# BOT-CPU.net
KiCad netlist of a schematic drawn in Altium Designer
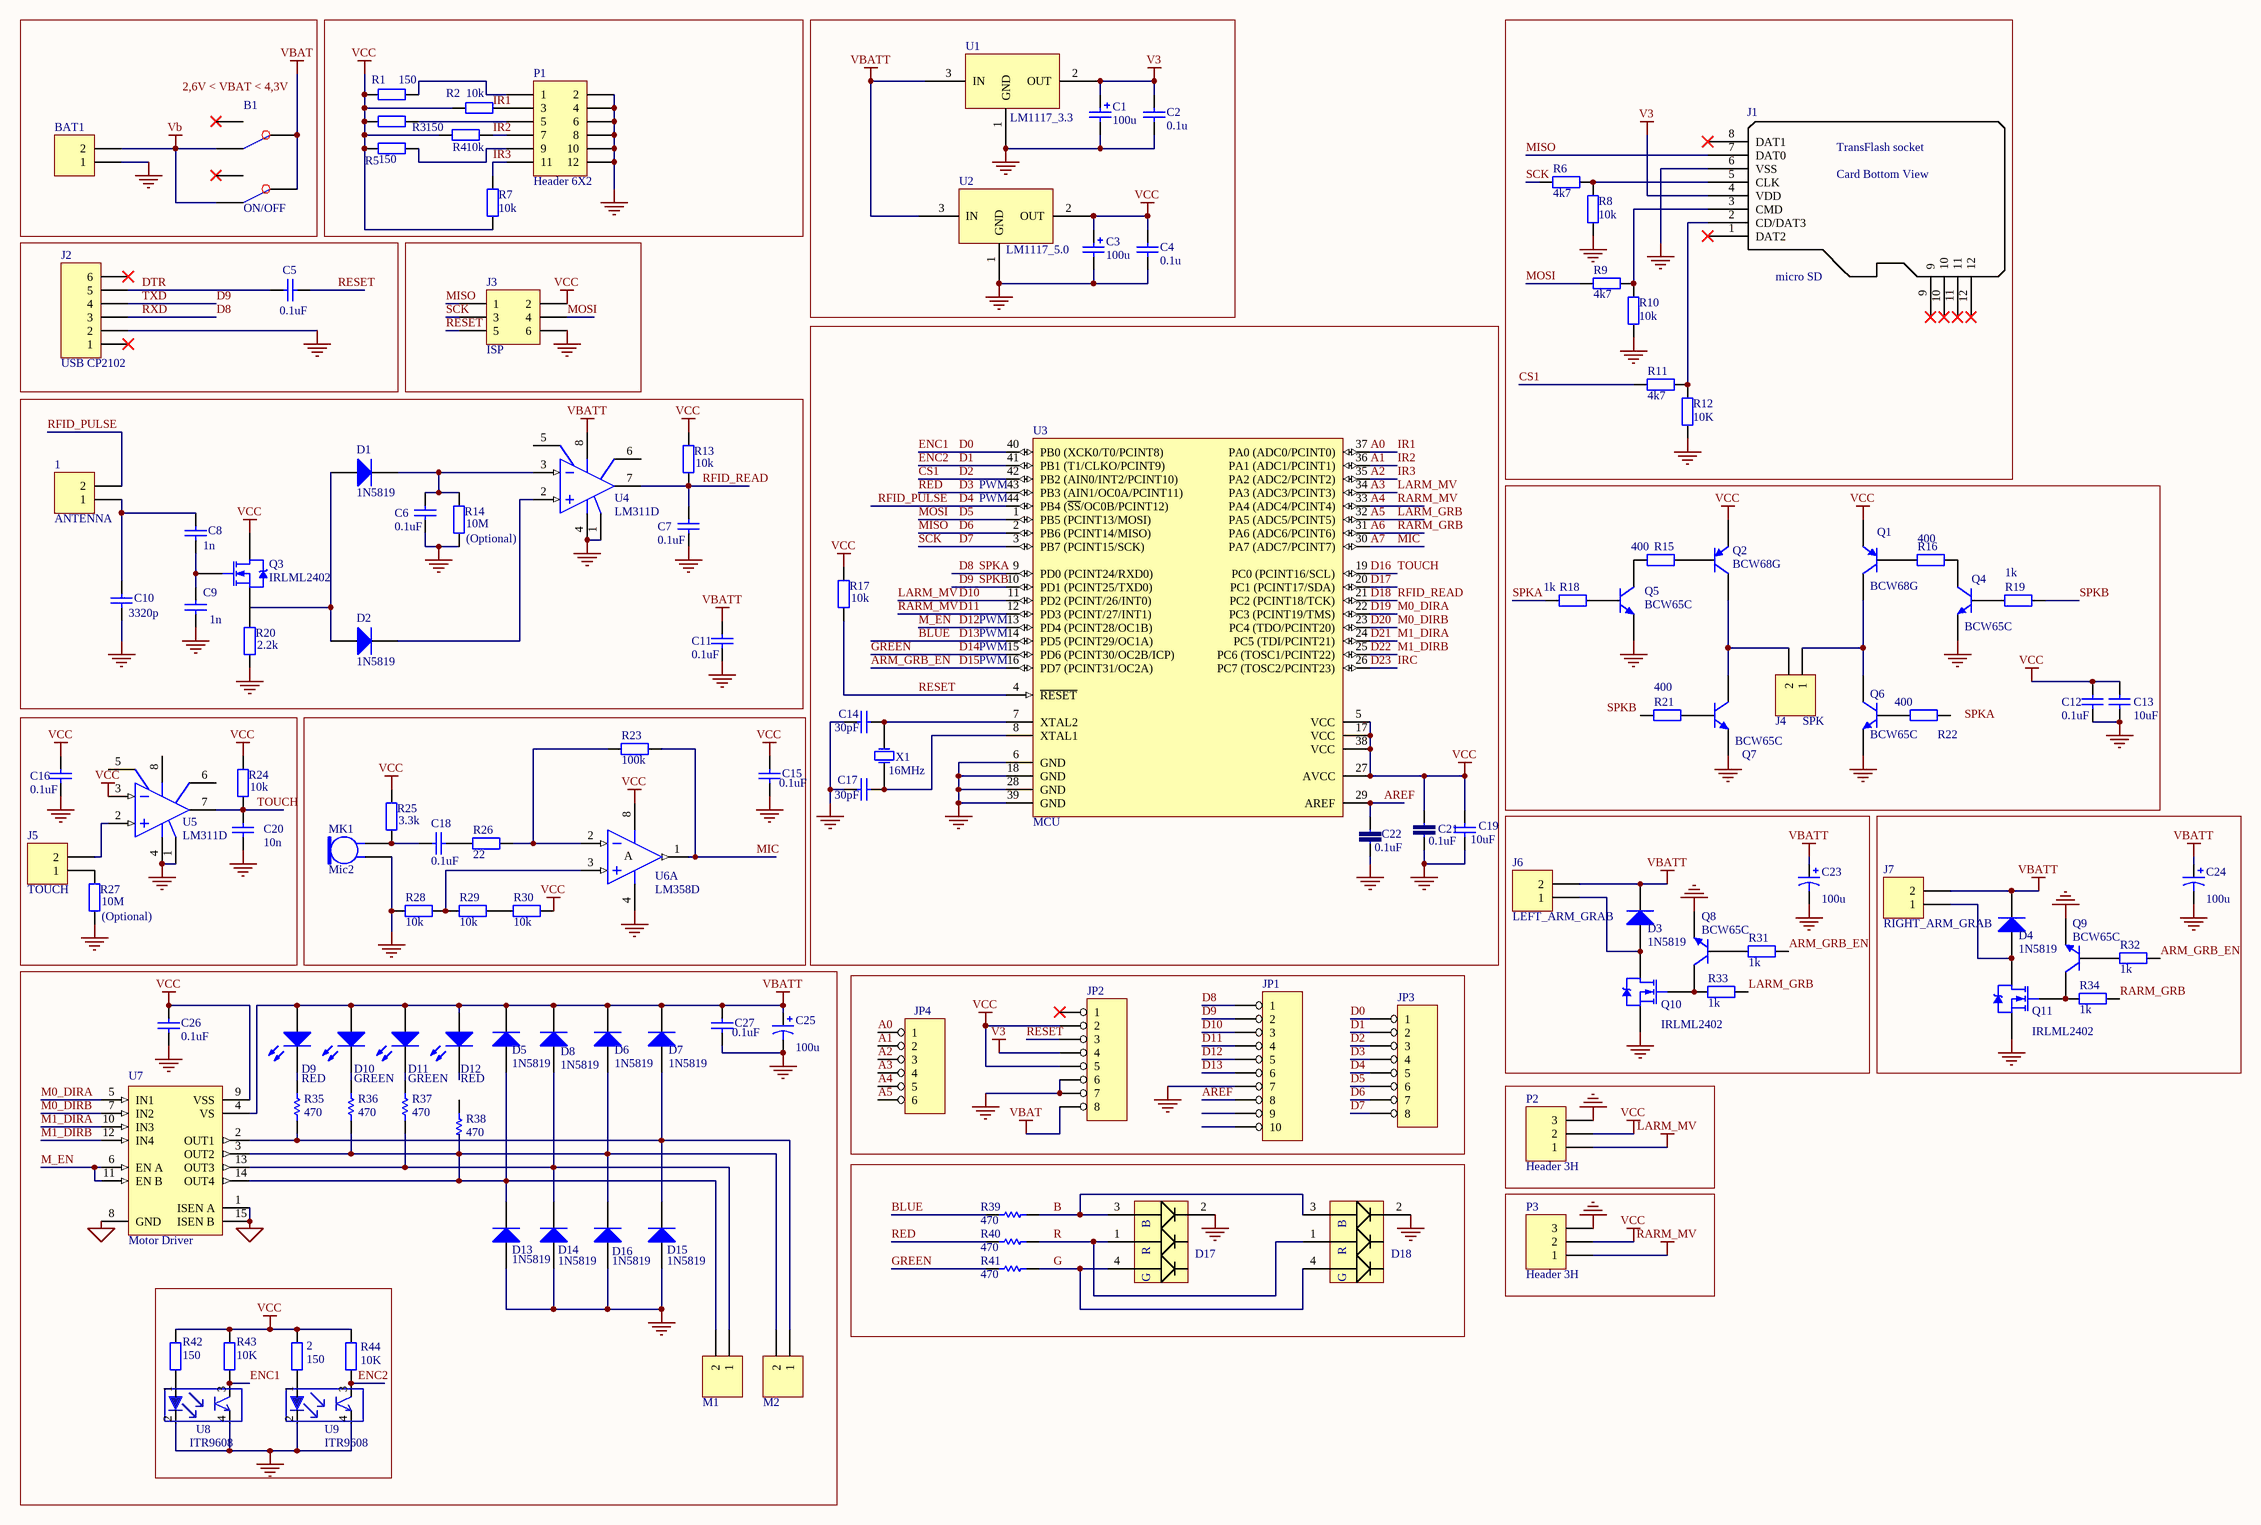
[diagram p0: BOT-CPU.SchDoc]

(export (version "E")
  (design (tool "Eeschema 10.0.6"))
  (components
    (comp (ref "1")
      (value "ANTENNA")
      (footprint "HDR1X2")
      (description "Header, 2-Pin")
      (fields (field (name "PUBLISHER") "Altium Limited"))
      (libsource (lib "*") (part "Header 2"))
    )
    (comp (ref "2")
      (value "150")
      (footprint "0805")
      (description "Resistor")
      (fields (field (name "Comment") "1K") (field (name "PUBLISHER") "Altium Limited"))
      (libsource (lib "") (part "Res2_2"))
    )
    (comp (ref "B1") (value "ON/OFF") (footprint "KGPS22F03") (libsource (lib "*") (part "Component_1")))
    (comp (ref "BAT1")
      (value "Header 2")
      (footprint "CP2D2.54")
      (description "Header, 2-Pin")
      (fields (field (name "PUBLISHER") "Altium Limited"))
      (libsource (lib "*") (part "Header 2"))
    )
    (comp (ref "C1")
      (value "100u")
      (footprint "C(D6.3*7)")
      (description "Polarized Capacitor (Axial)")
      (fields (field (name "ALTIUM_UNNAMED_1") "100u") (field (name "PUBLISHER") "Altium Limited"))
      (libsource (lib "*") (part "Cap Pol2"))
    )
    (comp (ref "C2")
      (value "0.1u")
      (footprint "0805")
      (description "Capacitor")
      (fields (field (name "PUBLISHER") "Altium Limited"))
      (libsource (lib "*") (part "Cap"))
    )
    (comp (ref "C3")
      (value "100u")
      (footprint "C(D6.3*7)")
      (description "Polarized Capacitor (Axial)")
      (fields (field (name "ALTIUM_UNNAMED_1") "100u") (field (name "PUBLISHER") "Altium Limited"))
      (libsource (lib "*") (part "Cap Pol2"))
    )
    (comp (ref "C4")
      (value "0.1u")
      (footprint "0805")
      (description "Capacitor")
      (fields (field (name "PUBLISHER") "Altium Limited"))
      (libsource (lib "*") (part "Cap"))
    )
    (comp (ref "C5")
      (value "0.1uF")
      (footprint "0805")
      (description "Capacitor")
      (fields (field (name "PUBLISHER") "*"))
      (libsource (lib "*") (part "Cap"))
    )
    (comp (ref "C6")
      (value "0.1uF")
      (footprint "0805")
      (description "Capacitor")
      (fields (field (name "PUBLISHER") "Altium Limited"))
      (libsource (lib "*") (part "Cap"))
    )
    (comp (ref "C7")
      (value "0.1uF")
      (footprint "0805")
      (description "Capacitor")
      (fields (field (name "PUBLISHER") "Altium Limited"))
      (libsource (lib "*") (part "Cap"))
    )
    (comp (ref "C8")
      (value "1n")
      (footprint "0805")
      (description "Capacitor")
      (fields (field (name "Comment") "1nF") (field (name "PUBLISHER") "Altium Limited"))
      (libsource (lib "*") (part "Cap"))
    )
    (comp (ref "C9")
      (value "1n")
      (footprint "0805")
      (description "Capacitor")
      (fields (field (name "Comment") "1nF") (field (name "PUBLISHER") "Altium Limited"))
      (libsource (lib "*") (part "Cap"))
    )
    (comp (ref "C10")
      (value "3320p")
      (footprint "0805")
      (description "Capacitor")
      (fields (field (name "Comment") "3320pF") (field (name "PUBLISHER") "Altium Limited"))
      (libsource (lib "*") (part "Cap"))
    )
    (comp (ref "C11")
      (value "0.1uF")
      (footprint "0805")
      (description "Capacitor")
      (fields (field (name "PUBLISHER") "Altium Limited"))
      (libsource (lib "*") (part "Cap"))
    )
    (comp (ref "C12")
      (value "0.1uF")
      (footprint "0805")
      (description "Capacitor")
      (fields (field (name "PUBLISHER") "Altium Limited"))
      (libsource (lib "*") (part "Cap"))
    )
    (comp (ref "C13")
      (value "10uF")
      (footprint "1206")
      (description "Capacitor")
      (fields (field (name "PUBLISHER") "Altium Limited"))
      (libsource (lib "*") (part "Cap"))
    )
    (comp (ref "C14")
      (value "30pF")
      (footprint "0805")
      (description "Capacitor")
      (fields (field (name "PUBLISHER") "Altium Limited"))
      (libsource (lib "*") (part "Cap"))
    )
    (comp (ref "C15")
      (value "0.1uF")
      (footprint "0805")
      (description "Capacitor")
      (fields (field (name "PUBLISHER") "Altium Limited"))
      (libsource (lib "*") (part "Cap"))
    )
    (comp (ref "C16")
      (value "0.1uF")
      (footprint "0805")
      (description "Capacitor")
      (fields (field (name "PUBLISHER") "Altium Limited"))
      (libsource (lib "*") (part "Cap"))
    )
    (comp (ref "C17")
      (value "30pF")
      (footprint "0805")
      (description "Capacitor")
      (fields (field (name "PUBLISHER") "Altium Limited"))
      (libsource (lib "*") (part "Cap"))
    )
    (comp (ref "C18")
      (value "0.1uF")
      (footprint "0805")
      (description "Capacitor")
      (fields (field (name "PUBLISHER") "Altium Limited"))
      (libsource (lib "") (part "Cap_1"))
    )
    (comp (ref "C19")
      (value "10uF")
      (footprint "1206")
      (description "Capacitor")
      (fields (field (name "PUBLISHER") "Altium Limited"))
      (libsource (lib "*") (part "Cap"))
    )
    (comp (ref "C20")
      (value "10n")
      (footprint "0805")
      (description "Capacitor")
      (fields (field (name "Comment") "0.1uF") (field (name "PUBLISHER") "Altium Limited"))
      (libsource (lib "*") (part "Cap"))
    )
    (comp (ref "C21") (value "0.1uF") (footprint "0805") (libsource (lib "*") (part "CAP0402")))
    (comp (ref "C22") (value "0.1uF") (footprint "0805") (libsource (lib "") (part "CAP0402_1")))
    (comp (ref "C23")
      (value "100u")
      (footprint "C(D6.3*7)")
      (description "Polarized Capacitor (Radial)")
      (fields (field (name "Comment") "220u") (field (name "PUBLISHER") "Altium Limited"))
      (libsource (lib "*") (part "Cap Pol1"))
    )
    (comp (ref "C24")
      (value "100u")
      (footprint "C(D6.3*7)")
      (description "Polarized Capacitor (Radial)")
      (fields (field (name "Comment") "220u") (field (name "PUBLISHER") "Altium Limited"))
      (libsource (lib "*") (part "Cap Pol1"))
    )
    (comp (ref "C25")
      (value "100u")
      (footprint "C(D6.3*7)")
      (description "Polarized Capacitor (Radial)")
      (fields (field (name "Comment") "220u") (field (name "PUBLISHER") "Altium Limited"))
      (libsource (lib "*") (part "Cap Pol1"))
    )
    (comp (ref "C26")
      (value "0.1uF")
      (footprint "0805")
      (description "Capacitor")
      (fields (field (name "PUBLISHER") "Altium Limited"))
      (libsource (lib "*") (part "Cap"))
    )
    (comp (ref "C27")
      (value "0.1uF")
      (footprint "0805")
      (description "Capacitor")
      (fields (field (name "PUBLISHER") "Altium Limited"))
      (libsource (lib "*") (part "Cap"))
    )
    (comp (ref "D1")
      (value "1N5819")
      (footprint "4007-smt")
      (description "Default Diode")
      (fields (field (name "PUBLISHER") "Altium Limited"))
      (libsource (lib "*") (part "Diode"))
    )
    (comp (ref "D2")
      (value "1N5819")
      (footprint "4007-smt")
      (description "Default Diode")
      (fields (field (name "PUBLISHER") "Altium Limited"))
      (libsource (lib "*") (part "Diode"))
    )
    (comp (ref "D3")
      (value "1N5819")
      (footprint "4007-smt")
      (description "Default Diode")
      (fields (field (name "PUBLISHER") "Altium Limited"))
      (libsource (lib "*") (part "Diode"))
    )
    (comp (ref "D4")
      (value "1N5819")
      (footprint "4007-smt")
      (description "Default Diode")
      (fields (field (name "PUBLISHER") "Altium Limited"))
      (libsource (lib "*") (part "Diode"))
    )
    (comp (ref "D5")
      (value "1N5819")
      (footprint "4007-smt")
      (description "Default Diode")
      (fields (field (name "PUBLISHER") "Altium Limited"))
      (libsource (lib "*") (part "Diode"))
    )
    (comp (ref "D6")
      (value "1N5819")
      (footprint "4007-smt")
      (description "Default Diode")
      (fields (field (name "PUBLISHER") "Altium Limited"))
      (libsource (lib "*") (part "Diode"))
    )
    (comp (ref "D7")
      (value "1N5819")
      (footprint "4007-smt")
      (description "Default Diode")
      (fields (field (name "PUBLISHER") "Altium Limited"))
      (libsource (lib "*") (part "Diode"))
    )
    (comp (ref "D8")
      (value "1N5819")
      (footprint "4007-smt")
      (description "Default Diode")
      (fields (field (name "PUBLISHER") "*"))
      (libsource (lib "*") (part "Diode"))
    )
    (comp (ref "D9")
      (value "RED")
      (footprint "LED-SMT")
      (description "Typical INFRARED GaAs LED")
      (fields (field (name "PUBLISHER") "Altium Limited"))
      (libsource (lib "*") (part "LED0"))
    )
    (comp (ref "D10")
      (value "GREEN")
      (footprint "LED-SMT")
      (description "Typical INFRARED GaAs LED")
      (fields (field (name "PUBLISHER") "Altium Limited"))
      (libsource (lib "*") (part "LED0"))
    )
    (comp (ref "D11")
      (value "GREEN")
      (footprint "LED-SMT")
      (description "Typical INFRARED GaAs LED")
      (fields (field (name "PUBLISHER") "Altium Limited"))
      (libsource (lib "*") (part "LED0"))
    )
    (comp (ref "D12")
      (value "RED")
      (footprint "LED-SMT")
      (description "Typical INFRARED GaAs LED")
      (fields (field (name "PUBLISHER") "Altium Limited"))
      (libsource (lib "*") (part "LED0"))
    )
    (comp (ref "D13")
      (value "1N5819")
      (footprint "4007-smt")
      (description "Default Diode")
      (fields (field (name "PUBLISHER") "Altium Limited"))
      (libsource (lib "*") (part "Diode"))
    )
    (comp (ref "D14")
      (value "1N5819")
      (footprint "4007-smt")
      (description "Default Diode")
      (fields (field (name "PUBLISHER") "Altium Limited"))
      (libsource (lib "*") (part "Diode"))
    )
    (comp (ref "D15")
      (value "1N5819")
      (footprint "4007-smt")
      (description "Default Diode")
      (fields (field (name "PUBLISHER") "Altium Limited"))
      (libsource (lib "*") (part "Diode"))
    )
    (comp (ref "D16")
      (value "1N5819")
      (footprint "4007-smt")
      (description "Default Diode")
      (fields (field (name "PUBLISHER") "Altium Limited"))
      (libsource (lib "*") (part "Diode"))
    )
    (comp (ref "D17") (value "RGB 5mm") (footprint "LED_RGB") (libsource (lib "*") (part "RGB PTH")))
    (comp (ref "D18") (value "RGB 5mm") (footprint "LED_RGB") (libsource (lib "*") (part "RGB PTH")))
    (comp (ref "J1")
      (value "micro SD")
      (footprint "MICRO_SD")
      (description "Transflash Socket")
      (libsource (lib "*") (part "JJ TRANSFLASH"))
    )
    (comp (ref "J2")
      (value "USB CP2102")
      (footprint "SIP6")
      (description "Header, 6-Pin")
      (fields (field (name "PUBLISHER") "Altium Limited"))
      (libsource (lib "*") (part "Header 6"))
    )
    (comp (ref "J3")
      (value "ISP")
      (footprint "con-6")
      (description "Header, 3-Pin, Dual row")
      (fields (field (name "PUBLISHER") "Altium Limited"))
      (libsource (lib "*") (part "Header 3X2"))
    )
    (comp (ref "J4")
      (value "SPK")
      (footprint "sip2")
      (description "Header, 2-Pin")
      (fields (field (name "PUBLISHER") "Altium Limited"))
      (libsource (lib "") (part "Header 2_1"))
    )
    (comp (ref "J5")
      (value "TOUCH")
      (footprint "HDR1X2")
      (description "Header, 2-Pin")
      (fields (field (name "PUBLISHER") "Altium Limited"))
      (libsource (lib "*") (part "Header 2"))
    )
    (comp (ref "J6")
      (value "LEFT_ARM_GRAB")
      (footprint "HDR1X2")
      (description "Header, 2-Pin")
      (fields (field (name "PUBLISHER") "Altium Limited"))
      (libsource (lib "*") (part "Header 2"))
    )
    (comp (ref "J7")
      (value "RIGHT_ARM_GRAB")
      (footprint "HDR1X2")
      (description "Header, 2-Pin")
      (fields (field (name "PUBLISHER") "Altium Limited"))
      (libsource (lib "*") (part "Header 2"))
    )
    (comp (ref "JP1") (value "PADS") (footprint "ARDUINO_10*1") (libsource (lib "*") (part "HEADER 10")))
    (comp (ref "JP2")
      (value "PADS")
      (footprint "ARDUINO_8*1")
      (description "8 Pin Header")
      (libsource (lib "*") (part "8 HEADER"))
    )
    (comp (ref "JP3")
      (value "PADS")
      (footprint "ARDUINO_8*1")
      (description "8 Pin Header")
      (libsource (lib "*") (part "8 HEADER"))
    )
    (comp (ref "JP4") (value "PADS") (footprint "ARDUINO_6*1") (libsource (lib "*") (part "HEADER 6")))
    (comp (ref "M1")
      (value "MOLEX")
      (footprint "CP2D2.54")
      (description "Header, 2-Pin")
      (fields (field (name "PUBLISHER") "Altium Limited"))
      (libsource (lib "") (part "Header 2_1"))
    )
    (comp (ref "M2")
      (value "MOLEX")
      (footprint "CP2D2.54")
      (description "Header, 2-Pin")
      (fields (field (name "PUBLISHER") "Altium Limited"))
      (libsource (lib "") (part "Header 2_1"))
    )
    (comp (ref "MK1")
      (value "Mic2")
      (footprint "MIC")
      (description "Microphone")
      (fields (field (name "PUBLISHER") "*"))
      (libsource (lib "*") (part "Mic2"))
    )
    (comp (ref "P1")
      (value "Header 6X2")
      (footprint "HDR2X6")
      (description "Header, 6-Pin, Dual row")
      (fields (field (name "PUBLISHER") "Altium Limited"))
      (libsource (lib "Miscellaneous Connectors") (part "Header 6X2"))
    )
    (comp (ref "P2")
      (value "Header 3H")
      (footprint "HDR1X3H")
      (description "Header, 3-Pin, Right Angle")
      (fields (field (name "PUBLISHER") "Altium Limited"))
      (libsource (lib "Miscellaneous Connectors") (part "Header 3H"))
    )
    (comp (ref "P3")
      (value "Header 3H")
      (footprint "HDR1X3H")
      (description "Header, 3-Pin, Right Angle")
      (fields (field (name "PUBLISHER") "Altium Limited"))
      (libsource (lib "Miscellaneous Connectors") (part "Header 3H"))
    )
    (comp (ref "Q1")
      (value "BCW68G")
      (footprint "SOT-23A_N")
      (description "PNP General Purpose Amplifier")
      (fields (field (name "PUBLISHER") "Altium Limited"))
      (libsource (lib "FSC Discrete BJT") (part "BCW68G"))
    )
    (comp (ref "Q2")
      (value "BCW68G")
      (footprint "SOT-23A_N")
      (description "PNP General Purpose Amplifier")
      (fields (field (name "PUBLISHER") "Altium Limited"))
      (libsource (lib "FSC Discrete BJT") (part "BCW68G"))
    )
    (comp (ref "Q3")
      (value "IRLML2402")
      (footprint "SOT-23_N")
      (description "HEXFET Power MOSFET")
      (fields (field (name "PUBLISHER") "Altium Limited"))
      (libsource (lib "IR Discrete MOSFET - Power") (part "IRLML2402"))
    )
    (comp (ref "Q4")
      (value "BCW65C")
      (footprint "SOT-23A_N")
      (description "NPN General Purpose Amplifier")
      (fields (field (name "PUBLISHER") "Altium Limited"))
      (libsource (lib "FSC Discrete BJT") (part "BCW65C"))
    )
    (comp (ref "Q5")
      (value "BCW65C")
      (footprint "SOT-23A_N")
      (description "NPN General Purpose Amplifier")
      (fields (field (name "PUBLISHER") "Altium Limited"))
      (libsource (lib "FSC Discrete BJT") (part "BCW65C"))
    )
    (comp (ref "Q6")
      (value "BCW65C")
      (footprint "SOT-23A_N")
      (description "NPN General Purpose Amplifier")
      (fields (field (name "PUBLISHER") "Altium Limited"))
      (libsource (lib "FSC Discrete BJT") (part "BCW65C"))
    )
    (comp (ref "Q7")
      (value "BCW65C")
      (footprint "SOT-23A_N")
      (description "NPN General Purpose Amplifier")
      (fields (field (name "PUBLISHER") "Altium Limited"))
      (libsource (lib "FSC Discrete BJT") (part "BCW65C"))
    )
    (comp (ref "Q8")
      (value "BCW65C")
      (footprint "SOT-23A_N")
      (description "NPN General Purpose Amplifier")
      (fields (field (name "PUBLISHER") "Altium Limited"))
      (libsource (lib "FSC Discrete BJT") (part "BCW65C"))
    )
    (comp (ref "Q9")
      (value "BCW65C")
      (footprint "SOT-23A_N")
      (description "NPN General Purpose Amplifier")
      (fields (field (name "PUBLISHER") "Altium Limited"))
      (libsource (lib "FSC Discrete BJT") (part "BCW65C"))
    )
    (comp (ref "Q10")
      (value "IRLML2402")
      (footprint "SOT-23_N")
      (description "HEXFET Power MOSFET")
      (fields (field (name "PUBLISHER") "Altium Limited"))
      (libsource (lib "IR Discrete MOSFET - Power") (part "IRLML2402"))
    )
    (comp (ref "Q11")
      (value "IRLML2402")
      (footprint "SOT-23_N")
      (description "HEXFET Power MOSFET")
      (fields (field (name "PUBLISHER") "Altium Limited"))
      (libsource (lib "IR Discrete MOSFET - Power") (part "IRLML2402"))
    )
    (comp (ref "R1")
      (value "150")
      (footprint "0805")
      (description "Resistor")
      (fields (field (name "PUBLISHER") "Altium Limited"))
      (libsource (lib "") (part "Res2_3"))
    )
    (comp (ref "R2")
      (value "10k")
      (footprint "0805")
      (description "Resistor")
      (fields (field (name "PUBLISHER") "Altium Limited"))
      (libsource (lib "") (part "Res2_3"))
    )
    (comp (ref "R3")
      (value "150")
      (footprint "0805")
      (description "Resistor")
      (fields (field (name "PUBLISHER") "Altium Limited"))
      (libsource (lib "") (part "Res2_3"))
    )
    (comp (ref "R4")
      (value "10k")
      (footprint "0805")
      (description "Resistor")
      (fields (field (name "PUBLISHER") "Altium Limited"))
      (libsource (lib "") (part "Res2_3"))
    )
    (comp (ref "R5")
      (value "150")
      (footprint "0805")
      (description "Resistor")
      (fields (field (name "PUBLISHER") "Altium Limited"))
      (libsource (lib "") (part "Res2_3"))
    )
    (comp (ref "R6")
      (value "4k7")
      (footprint "0805")
      (description "Resistor")
      (fields (field (name "PUBLISHER") "Altium Limited"))
      (libsource (lib "*") (part "Res2"))
    )
    (comp (ref "R7")
      (value "10k")
      (footprint "0805")
      (description "Resistor")
      (fields (field (name "PUBLISHER") "Altium Limited"))
      (libsource (lib "") (part "Res2_2"))
    )
    (comp (ref "R8")
      (value "10k")
      (footprint "0805")
      (description "Resistor")
      (fields (field (name "PUBLISHER") "Altium Limited"))
      (libsource (lib "") (part "Res2_1"))
    )
    (comp (ref "R9")
      (value "4k7")
      (footprint "0805")
      (description "Resistor")
      (fields (field (name "Comment") "10k") (field (name "PUBLISHER") "Altium Limited"))
      (libsource (lib "*") (part "Res2"))
    )
    (comp (ref "R10")
      (value "10k")
      (footprint "0805")
      (description "Resistor")
      (fields (field (name "Comment") "20K") (field (name "PUBLISHER") "Altium Limited"))
      (libsource (lib "") (part "Res2_1"))
    )
    (comp (ref "R11")
      (value "4k7")
      (footprint "0805")
      (description "Resistor")
      (fields (field (name "Comment") "10k") (field (name "PUBLISHER") "Altium Limited"))
      (libsource (lib "") (part "Res2_1"))
    )
    (comp (ref "R12")
      (value "10K")
      (footprint "0805")
      (description "Resistor")
      (fields (field (name "PUBLISHER") "Altium Limited"))
      (libsource (lib "*") (part "Res2"))
    )
    (comp (ref "R13")
      (value "10k")
      (footprint "0805")
      (description "Resistor")
      (fields (field (name "PUBLISHER") "Altium Limited"))
      (libsource (lib "*") (part "Res2"))
    )
    (comp (ref "R14")
      (value "(Optional)")
      (footprint "0805")
      (description "Resistor")
      (fields (field (name "ALTIUM_VALUE") "10M") (field (name "PUBLISHER") "Altium Limited"))
      (libsource (lib "*") (part "Res2"))
    )
    (comp (ref "R15")
      (value "400")
      (footprint "0805")
      (description "Resistor")
      (fields (field (name "PUBLISHER") "Altium Limited"))
      (libsource (lib "") (part "Res2_3"))
    )
    (comp (ref "R16")
      (value "400")
      (footprint "0805")
      (description "Resistor")
      (fields (field (name "PUBLISHER") "Altium Limited"))
      (libsource (lib "*") (part "Res2"))
    )
    (comp (ref "R17")
      (value "10k")
      (footprint "0805")
      (description "Resistor")
      (fields (field (name "Comment") "2.2k") (field (name "PUBLISHER") "Altium Limited"))
      (libsource (lib "*") (part "Res2"))
    )
    (comp (ref "R18")
      (value "1k")
      (footprint "0805")
      (description "Resistor")
      (fields (field (name "Comment") "1K") (field (name "PUBLISHER") "Altium Limited"))
      (libsource (lib "") (part "Res2_3"))
    )
    (comp (ref "R19")
      (value "1k")
      (footprint "0805")
      (description "Resistor")
      (fields (field (name "Comment") "1K") (field (name "PUBLISHER") "Altium Limited"))
      (libsource (lib "*") (part "Res2"))
    )
    (comp (ref "R20")
      (value "2.2k")
      (footprint "0805")
      (description "Resistor")
      (fields (field (name "PUBLISHER") "Altium Limited"))
      (libsource (lib "*") (part "Res2"))
    )
    (comp (ref "R21")
      (value "400")
      (footprint "0805")
      (description "Resistor")
      (fields (field (name "PUBLISHER") "Altium Limited"))
      (libsource (lib "") (part "Res2_3"))
    )
    (comp (ref "R22")
      (value "400")
      (footprint "0805")
      (description "Resistor")
      (fields (field (name "PUBLISHER") "Altium Limited"))
      (libsource (lib "*") (part "Res2"))
    )
    (comp (ref "R23")
      (value "100k")
      (footprint "0805")
      (description "Resistor")
      (fields (field (name "Comment") "1M") (field (name "PUBLISHER") "Altium Limited"))
      (libsource (lib "") (part "Res2_3"))
    )
    (comp (ref "R24")
      (value "10k")
      (footprint "0805")
      (description "Resistor")
      (fields (field (name "PUBLISHER") "Altium Limited"))
      (libsource (lib "*") (part "Res2"))
    )
    (comp (ref "R25")
      (value "3.3k")
      (footprint "0805")
      (description "Resistor")
      (fields (field (name "PUBLISHER") "Altium Limited"))
      (libsource (lib "*") (part "Res2"))
    )
    (comp (ref "R26")
      (value "22")
      (footprint "0805")
      (description "Resistor")
      (fields (field (name "PUBLISHER") "Altium Limited"))
      (libsource (lib "") (part "Res2_3"))
    )
    (comp (ref "R27")
      (value "(Optional)")
      (footprint "0805")
      (description "Resistor")
      (fields (field (name "ALTIUM_VALUE") "10M") (field (name "PUBLISHER") "Altium Limited"))
      (libsource (lib "*") (part "Res2"))
    )
    (comp (ref "R28")
      (value "10k")
      (footprint "0805")
      (description "Resistor")
      (fields (field (name "PUBLISHER") "Altium Limited"))
      (libsource (lib "") (part "Res2_3"))
    )
    (comp (ref "R29")
      (value "10k")
      (footprint "0805")
      (description "Resistor")
      (fields (field (name "PUBLISHER") "Altium Limited"))
      (libsource (lib "") (part "Res2_3"))
    )
    (comp (ref "R30")
      (value "10k")
      (footprint "0805")
      (description "Resistor")
      (fields (field (name "PUBLISHER") "Altium Limited"))
      (libsource (lib "") (part "Res2_3"))
    )
    (comp (ref "R31")
      (value "1k")
      (footprint "0805")
      (description "Resistor")
      (fields (field (name "Comment") "2.2k") (field (name "PUBLISHER") "Altium Limited"))
      (libsource (lib "") (part "Res2_3"))
    )
    (comp (ref "R32")
      (value "1k")
      (footprint "0805")
      (description "Resistor")
      (fields (field (name "Comment") "2.2k") (field (name "PUBLISHER") "Altium Limited"))
      (libsource (lib "") (part "Res2_3"))
    )
    (comp (ref "R33")
      (value "1k")
      (footprint "0805")
      (description "Resistor")
      (fields (field (name "Comment") "2.2k") (field (name "PUBLISHER") "Altium Limited"))
      (libsource (lib "") (part "Res2_3"))
    )
    (comp (ref "R34")
      (value "1k")
      (footprint "0805")
      (description "Resistor")
      (fields (field (name "Comment") "2.2k") (field (name "PUBLISHER") "Altium Limited"))
      (libsource (lib "") (part "Res2_3"))
    )
    (comp (ref "R35")
      (value "470")
      (footprint "0805")
      (description "Resistor")
      (fields (field (name "PUBLISHER") "Altium Limited"))
      (libsource (lib "*") (part "Res1"))
    )
    (comp (ref "R36")
      (value "470")
      (footprint "0805")
      (description "Resistor")
      (fields (field (name "PUBLISHER") "Altium Limited"))
      (libsource (lib "*") (part "Res1"))
    )
    (comp (ref "R37")
      (value "470")
      (footprint "0805")
      (description "Resistor")
      (fields (field (name "PUBLISHER") "Altium Limited"))
      (libsource (lib "*") (part "Res1"))
    )
    (comp (ref "R38")
      (value "470")
      (footprint "0805")
      (description "Resistor")
      (fields (field (name "PUBLISHER") "Altium Limited"))
      (libsource (lib "*") (part "Res1"))
    )
    (comp (ref "R39")
      (value "470")
      (footprint "0805")
      (description "Resistor")
      (fields (field (name "Comment") "560") (field (name "PUBLISHER") "Altium Limited"))
      (libsource (lib "*") (part "Res1"))
    )
    (comp (ref "R40")
      (value "470")
      (footprint "0805")
      (description "Resistor")
      (fields (field (name "PUBLISHER") "Altium Limited"))
      (libsource (lib "*") (part "Res1"))
    )
    (comp (ref "R41")
      (value "470")
      (footprint "0805")
      (description "Resistor")
      (fields (field (name "PUBLISHER") "Altium Limited"))
      (libsource (lib "*") (part "Res1"))
    )
    (comp (ref "R42")
      (value "150")
      (footprint "0805")
      (description "Resistor")
      (fields (field (name "Comment") "1K") (field (name "PUBLISHER") "Altium Limited"))
      (libsource (lib "") (part "Res2_2"))
    )
    (comp (ref "R43")
      (value "10K")
      (footprint "0805")
      (description "Resistor")
      (fields (field (name "Comment") "1K") (field (name "PUBLISHER") "Altium Limited"))
      (libsource (lib "") (part "Res2_2"))
    )
    (comp (ref "R44")
      (value "10K")
      (footprint "0805")
      (description "Resistor")
      (fields (field (name "Comment") "1K") (field (name "PUBLISHER") "Altium Limited"))
      (libsource (lib "") (part "Res2_2"))
    )
    (comp (ref "U1") (value "LM1117_3.3") (footprint "LM1117") (libsource (lib "*") (part "LM1117")))
    (comp (ref "U2") (value "LM1117_5.0") (footprint "LM1117") (libsource (lib "*") (part "LM1117")))
    (comp (ref "U3")
      (value "MCU")
      (footprint "QFP44")
      (description "8-bit AVR Microcontroller, 2.7-5.5V, 20MHz, 64KB Flash, 2KB EEPROM, 4KB SRAM, 44-pin TQFP")
      (libsource (lib "*") (part "ATmega644-20AU"))
    )
    (comp (ref "U4")
      (value "LM311D")
      (footprint "SO8_N")
      (description "Voltage Comparator")
      (fields (field (name "PUBLISHER") "Altium Limited"))
      (libsource (lib "ST Analog Comparator") (part "LM311D"))
    )
    (comp (ref "U5")
      (value "LM311D")
      (footprint "SO8_N")
      (description "Voltage Comparator")
      (fields (field (name "PUBLISHER") "Altium Limited"))
      (libsource (lib "ST Analog Comparator") (part "LM311D"))
    )
    (comp (ref "U6")
      (value "LM358D")
      (footprint "D008_L")
      (description "Dual Operational Amplifier")
      (fields (field (name "PUBLISHER") "Altium Limited"))
      (libsource (lib "TI Operational Amplifier") (part "LM358D"))
    )
    (comp (ref "U7")
      (value "Motor Driver")
      (footprint "L298N")
      (description "Dual Full Bridge Driver")
      (fields (field (name "PUBLISHER") "Altium Limited"))
      (libsource (lib "*") (part "L298N"))
    )
    (comp (ref "U8") (value "ITR9608") (footprint "ITR9608") (libsource (lib "*") (part "ITR9608")))
    (comp (ref "U9") (value "ITR9608") (footprint "ITR9608") (libsource (lib "*") (part "ITR9608")))
    (comp (ref "X1")
      (value "16MHz")
      (footprint "XTAL2")
      (description "Crystal Oscillator")
      (fields (field (name "PUBLISHER") "Altium Limited"))
      (libsource (lib "*") (part "XTAL"))
    )
  )
  (nets
    (net (code "1") (name "/A0") (class "Default")
      (node (ref "JP4") (pin "1") (pinfunction "1_1") (pintype "passive"))
      (node (ref "U3") (pin "37") (pinfunction "PA0_(ADC0/PCINT0)_37") (pintype "bidirectional"))
    )
    (net (code "2") (name "/A1") (class "Default")
      (node (ref "JP4") (pin "2") (pinfunction "2_2") (pintype "passive"))
      (node (ref "P1") (pin "7") (pinfunction "7_7") (pintype "passive"))
      (node (ref "R4") (pin "2") (pinfunction "2_2") (pintype "passive"))
      (node (ref "U3") (pin "36") (pinfunction "PA1_(ADC1/PCINT1)_36") (pintype "bidirectional"))
    )
    (net (code "3") (name "/A2") (class "Default")
      (node (ref "JP4") (pin "3") (pinfunction "3_3") (pintype "passive"))
      (node (ref "P1") (pin "11") (pinfunction "11_11") (pintype "passive"))
      (node (ref "R7") (pin "2") (pinfunction "2_2") (pintype "passive"))
      (node (ref "U3") (pin "35") (pinfunction "PA2_(ADC2/PCINT2)_35") (pintype "bidirectional"))
    )
    (net (code "4") (name "/A5") (class "Default")
      (node (ref "JP4") (pin "6") (pinfunction "6_6") (pintype "passive"))
      (node (ref "R33") (pin "2") (pinfunction "2_2") (pintype "passive"))
      (node (ref "U3") (pin "32") (pinfunction "PA5_(ADC5/PCINT5)_32") (pintype "bidirectional"))
    )
    (net (code "5") (name "/A6") (class "Default")
      (node (ref "R34") (pin "2") (pinfunction "2_2") (pintype "passive"))
      (node (ref "U3") (pin "31") (pinfunction "PA6_(ADC6/PCINT6)_31") (pintype "bidirectional"))
    )
    (net (code "6") (name "/A7") (class "Default")
      (node (ref "R23") (pin "2") (pinfunction "2_2") (pintype "passive"))
      (node (ref "U3") (pin "30") (pinfunction "PA7_(ADC7/PCINT7)_30") (pintype "bidirectional"))
      (node (ref "U6") (pin "1") (pinfunction "OUT_1") (pintype "output"))
    )
    (net (code "7") (name "/AREF") (class "Default")
      (node (ref "C22") (pin "2") (pinfunction "2_2") (pintype "passive"))
      (node (ref "JP1") (pin "8") (pinfunction "8_8") (pintype "passive"))
      (node (ref "U3") (pin "29") (pinfunction "AREF_29") (pintype "passive"))
    )
    (net (code "8") (name "/ARM_GRB_EN") (class "Default")
      (node (ref "R31") (pin "2") (pinfunction "2_2") (pintype "passive"))
      (node (ref "R32") (pin "2") (pinfunction "2_2") (pintype "passive"))
      (node (ref "U3") (pin "16") (pinfunction "PD7_(PCINT31/OC2A)_16") (pintype "bidirectional"))
    )
    (net (code "9") (name "/B") (class "Default")
      (node (ref "D17") (pin "3") (pinfunction "3_3") (pintype "passive"))
      (node (ref "D18") (pin "3") (pinfunction "3_3") (pintype "passive"))
      (node (ref "R39") (pin "2") (pinfunction "2_2") (pintype "passive"))
    )
    (net (code "10") (name "/BLUE") (class "Default")
      (node (ref "JP1") (pin "6") (pinfunction "6_6") (pintype "passive"))
      (node (ref "R39") (pin "1") (pinfunction "1_1") (pintype "passive"))
      (node (ref "U3") (pin "14") (pinfunction "PD5_(PCINT29/OC1A)_14") (pintype "bidirectional"))
    )
    (net (code "11") (name "/CS1") (class "Default")
      (node (ref "JP3") (pin "3") (pinfunction "3_3") (pintype "passive"))
      (node (ref "R11") (pin "2") (pinfunction "2_2") (pintype "passive"))
      (node (ref "U3") (pin "42") (pinfunction "PB2_(AIN0/INT2/PCINT10)_42") (pintype "bidirectional"))
    )
    (net (code "12") (name "/D0") (class "Default")
      (node (ref "JP3") (pin "1") (pinfunction "1_1") (pintype "passive"))
      (node (ref "R43") (pin "1") (pinfunction "1_1") (pintype "passive"))
      (node (ref "U3") (pin "40") (pinfunction "PB0_(XCK0/T0/PCINT8)_40") (pintype "bidirectional"))
      (node (ref "U8") (pin "3") (pinfunction "COLLECTOR_3") (pintype "passive"))
    )
    (net (code "13") (name "/D1") (class "Default")
      (node (ref "JP3") (pin "2") (pinfunction "2_2") (pintype "passive"))
      (node (ref "R44") (pin "1") (pinfunction "1_1") (pintype "passive"))
      (node (ref "U3") (pin "41") (pinfunction "PB1_(T1/CLKO/PCINT9)_41") (pintype "bidirectional"))
      (node (ref "U9") (pin "3") (pinfunction "COLLECTOR_3") (pintype "passive"))
    )
    (net (code "14") (name "/D3") (class "Default")
      (node (ref "JP3") (pin "4") (pinfunction "4_4") (pintype "passive"))
      (node (ref "R40") (pin "1") (pinfunction "1_1") (pintype "passive"))
      (node (ref "U3") (pin "43") (pinfunction "PB3_(AIN1/OC0A/PCINT11)_43") (pintype "bidirectional"))
    )
    (net (code "15") (name "/D4") (class "Default")
      (node (ref "1") (pin "2") (pinfunction "2_2") (pintype "passive"))
      (node (ref "JP3") (pin "5") (pinfunction "5_5") (pintype "passive"))
      (node (ref "U3") (pin "44") (pinfunction "PB4_(~{SS}/OC0B/PCINT12)_44") (pintype "bidirectional"))
    )
    (net (code "16") (name "/D5") (class "Default")
      (node (ref "J3") (pin "4") (pinfunction "4_4") (pintype "passive"))
      (node (ref "JP3") (pin "6") (pinfunction "6_6") (pintype "passive"))
      (node (ref "R9") (pin "2") (pinfunction "2_2") (pintype "passive"))
      (node (ref "U3") (pin "1") (pinfunction "PB5_(PCINT13/MOSI)_1") (pintype "bidirectional"))
    )
    (net (code "17") (name "/D6") (class "Default")
      (node (ref "J1") (pin "7") (pinfunction "DAT0_7") (pintype "passive"))
      (node (ref "J3") (pin "1") (pinfunction "1_1") (pintype "passive"))
      (node (ref "JP3") (pin "7") (pinfunction "7_7") (pintype "passive"))
      (node (ref "U3") (pin "2") (pinfunction "PB6_(PCINT14/MISO)_2") (pintype "bidirectional"))
    )
    (net (code "18") (name "/D7") (class "Default")
      (node (ref "J3") (pin "3") (pinfunction "3_3") (pintype "passive"))
      (node (ref "JP3") (pin "8") (pinfunction "8_8") (pintype "passive"))
      (node (ref "R6") (pin "2") (pinfunction "2_2") (pintype "passive"))
      (node (ref "U3") (pin "3") (pinfunction "PB7_(PCINT15/SCK)_3") (pintype "bidirectional"))
    )
    (net (code "19") (name "/D8") (class "Default")
      (node (ref "J2") (pin "3") (pinfunction "3_3") (pintype "passive"))
      (node (ref "JP1") (pin "1") (pinfunction "1_1") (pintype "passive"))
      (node (ref "R18") (pin "1") (pinfunction "1_1") (pintype "passive"))
      (node (ref "U3") (pin "9") (pinfunction "PD0_(PCINT24/RXD0)_9") (pintype "bidirectional"))
    )
    (net (code "20") (name "/D9") (class "Default")
      (node (ref "J2") (pin "4") (pinfunction "4_4") (pintype "passive"))
      (node (ref "JP1") (pin "2") (pinfunction "2_2") (pintype "passive"))
      (node (ref "R19") (pin "1") (pinfunction "1_1") (pintype "passive"))
      (node (ref "U3") (pin "10") (pinfunction "PD1_(PCINT25/TXD0)_10") (pintype "bidirectional"))
    )
    (net (code "21") (name "/D12") (class "Default")
      (node (ref "JP1") (pin "5") (pinfunction "5_5") (pintype "passive"))
      (node (ref "U3") (pin "13") (pinfunction "PD4_(PCINT28/OC1B)_13") (pintype "bidirectional"))
      (node (ref "U7") (pin "11") (pinfunction "EN_B_11") (pintype "input"))
      (node (ref "U7") (pin "6") (pinfunction "EN_A_6") (pintype "input"))
    )
    (net (code "22") (name "/D14") (class "Default")
      (node (ref "R41") (pin "1") (pinfunction "1_1") (pintype "passive"))
      (node (ref "U3") (pin "15") (pinfunction "PD6_(PCINT30/OC2B/ICP)_15") (pintype "bidirectional"))
    )
    (net (code "23") (name "/D16") (class "Default")
      (node (ref "C20") (pin "2") (pinfunction "2_2") (pintype "passive"))
      (node (ref "R24") (pin "2") (pinfunction "2_2") (pintype "passive"))
      (node (ref "U3") (pin "19") (pinfunction "PC0_(PCINT16/SCL)_19") (pintype "bidirectional"))
      (node (ref "U5") (pin "7") (pinfunction "OUT_7") (pintype "open_collector"))
    )
    (net (code "24") (name "/D17") (class "Default")
      (node (ref "U3") (pin "20") (pinfunction "PC1_(PCINT17/SDA)_20") (pintype "bidirectional"))
    )
    (net (code "25") (name "/D18") (class "Default")
      (node (ref "C7") (pin "2") (pinfunction "2_2") (pintype "passive"))
      (node (ref "R13") (pin "2") (pinfunction "2_2") (pintype "passive"))
      (node (ref "U3") (pin "21") (pinfunction "PC2_(PCINT18/TCK)_21") (pintype "bidirectional"))
      (node (ref "U4") (pin "7") (pinfunction "OUT_7") (pintype "open_collector"))
    )
    (net (code "26") (name "/D19") (class "Default")
      (node (ref "U3") (pin "22") (pinfunction "PC3_(PCINT19/TMS)_22") (pintype "bidirectional"))
      (node (ref "U7") (pin "5") (pinfunction "IN1_5") (pintype "input"))
    )
    (net (code "27") (name "/D20") (class "Default")
      (node (ref "U3") (pin "23") (pinfunction "PC4_(TDO/PCINT20)_23") (pintype "bidirectional"))
      (node (ref "U7") (pin "7") (pinfunction "IN2_7") (pintype "input"))
    )
    (net (code "28") (name "/D21") (class "Default")
      (node (ref "U3") (pin "24") (pinfunction "PC5_(TDI/PCINT21)_24") (pintype "bidirectional"))
      (node (ref "U7") (pin "10") (pinfunction "IN3_10") (pintype "input"))
    )
    (net (code "29") (name "/D22") (class "Default")
      (node (ref "U3") (pin "25") (pinfunction "PC6_(TOSC1/PCINT22)_25") (pintype "bidirectional"))
      (node (ref "U7") (pin "12") (pinfunction "IN4_12") (pintype "input"))
    )
    (net (code "30") (name "/D23") (class "Default")
      (node (ref "U3") (pin "26") (pinfunction "PC7_(TOSC2/PCINT23)_26") (pintype "bidirectional"))
    )
    (net (code "31") (name "/DTR") (class "Default")
      (node (ref "C5") (pin "1") (pinfunction "1_1") (pintype "passive"))
      (node (ref "J2") (pin "5") (pinfunction "5_5") (pintype "passive"))
    )
    (net (code "32") (name "/G") (class "Default")
      (node (ref "D17") (pin "4") (pinfunction "4_4") (pintype "passive"))
      (node (ref "D18") (pin "4") (pinfunction "4_4") (pintype "passive"))
      (node (ref "R41") (pin "2") (pinfunction "2_2") (pintype "passive"))
    )
    (net (code "33") (name "/R") (class "Default")
      (node (ref "D17") (pin "1") (pinfunction "1_1") (pintype "passive"))
      (node (ref "D18") (pin "1") (pinfunction "1_1") (pintype "passive"))
      (node (ref "R40") (pin "2") (pinfunction "2_2") (pintype "passive"))
    )
    (net (code "34") (name "/RESET") (class "Default")
      (node (ref "C5") (pin "2") (pinfunction "2_2") (pintype "passive"))
      (node (ref "J3") (pin "5") (pinfunction "5_5") (pintype "passive"))
      (node (ref "JP2") (pin "3") (pinfunction "3_3") (pintype "passive"))
      (node (ref "R17") (pin "2") (pinfunction "2_2") (pintype "passive"))
      (node (ref "U3") (pin "4") (pinfunction "~{RESET}_4") (pintype "input"))
    )
    (net (code "35") (name "GND") (class "Default")
      (node (ref "BAT1") (pin "1") (pinfunction "1_1") (pintype "passive"))
      (node (ref "C1") (pin "2") (pinfunction "2_2") (pintype "passive"))
      (node (ref "C10") (pin "1") (pinfunction "1_1") (pintype "passive"))
      (node (ref "C11") (pin "1") (pinfunction "1_1") (pintype "passive"))
      (node (ref "C12") (pin "1") (pinfunction "1_1") (pintype "passive"))
      (node (ref "C13") (pin "1") (pinfunction "1_1") (pintype "passive"))
      (node (ref "C14") (pin "1") (pinfunction "1_1") (pintype "passive"))
      (node (ref "C15") (pin "2") (pinfunction "2_2") (pintype "passive"))
      (node (ref "C16") (pin "1") (pinfunction "1_1") (pintype "passive"))
      (node (ref "C17") (pin "1") (pinfunction "1_1") (pintype "passive"))
      (node (ref "C19") (pin "1") (pinfunction "1_1") (pintype "passive"))
      (node (ref "C2") (pin "1") (pinfunction "1_1") (pintype "passive"))
      (node (ref "C20") (pin "1") (pinfunction "1_1") (pintype "passive"))
      (node (ref "C21") (pin "1") (pinfunction "1_1") (pintype "passive"))
      (node (ref "C22") (pin "1") (pinfunction "1_1") (pintype "passive"))
      (node (ref "C23") (pin "2") (pinfunction "2_2") (pintype "passive"))
      (node (ref "C24") (pin "2") (pinfunction "2_2") (pintype "passive"))
      (node (ref "C25") (pin "2") (pinfunction "2_2") (pintype "passive"))
      (node (ref "C26") (pin "2") (pinfunction "2_2") (pintype "passive"))
      (node (ref "C27") (pin "2") (pinfunction "2_2") (pintype "passive"))
      (node (ref "C3") (pin "2") (pinfunction "2_2") (pintype "passive"))
      (node (ref "C4") (pin "1") (pinfunction "1_1") (pintype "passive"))
      (node (ref "C6") (pin "1") (pinfunction "1_1") (pintype "passive"))
      (node (ref "C7") (pin "1") (pinfunction "1_1") (pintype "passive"))
      (node (ref "C9") (pin "1") (pinfunction "1_1") (pintype "passive"))
      (node (ref "D13") (pin "1") (pinfunction "A_1") (pintype "passive"))
      (node (ref "D14") (pin "1") (pinfunction "A_1") (pintype "passive"))
      (node (ref "D15") (pin "1") (pinfunction "A_1") (pintype "passive"))
      (node (ref "D16") (pin "1") (pinfunction "A_1") (pintype "passive"))
      (node (ref "D17") (pin "2") (pinfunction "2_2") (pintype "passive"))
      (node (ref "D18") (pin "2") (pinfunction "2_2") (pintype "passive"))
      (node (ref "J1") (pin "6") (pinfunction "VSS_6") (pintype "passive"))
      (node (ref "J2") (pin "2") (pinfunction "2_2") (pintype "passive"))
      (node (ref "J3") (pin "6") (pinfunction "6_6") (pintype "passive"))
      (node (ref "JP1") (pin "7") (pinfunction "7_7") (pintype "passive"))
      (node (ref "JP2") (pin "6") (pinfunction "6_6") (pintype "passive"))
      (node (ref "JP2") (pin "7") (pinfunction "7_7") (pintype "passive"))
      (node (ref "MK1") (pin "2") (pinfunction "2_2") (pintype "passive"))
      (node (ref "P1") (pin "10") (pinfunction "10_10") (pintype "passive"))
      (node (ref "P1") (pin "12") (pinfunction "12_12") (pintype "passive"))
      (node (ref "P1") (pin "2") (pinfunction "2_2") (pintype "passive"))
      (node (ref "P1") (pin "4") (pinfunction "4_4") (pintype "passive"))
      (node (ref "P1") (pin "6") (pinfunction "6_6") (pintype "passive"))
      (node (ref "P1") (pin "8") (pinfunction "8_8") (pintype "passive"))
      (node (ref "P2") (pin "3") (pinfunction "3_3") (pintype "passive"))
      (node (ref "P3") (pin "3") (pinfunction "3_3") (pintype "passive"))
      (node (ref "Q10") (pin "2") (pinfunction "S_2") (pintype "passive"))
      (node (ref "Q11") (pin "2") (pinfunction "S_2") (pintype "passive"))
      (node (ref "Q4") (pin "2") (pinfunction "E_2") (pintype "passive"))
      (node (ref "Q5") (pin "2") (pinfunction "E_2") (pintype "passive"))
      (node (ref "Q6") (pin "2") (pinfunction "E_2") (pintype "passive"))
      (node (ref "Q7") (pin "2") (pinfunction "E_2") (pintype "passive"))
      (node (ref "Q8") (pin "2") (pinfunction "E_2") (pintype "passive"))
      (node (ref "Q9") (pin "2") (pinfunction "E_2") (pintype "passive"))
      (node (ref "R10") (pin "2") (pinfunction "2_2") (pintype "passive"))
      (node (ref "R12") (pin "2") (pinfunction "2_2") (pintype "passive"))
      (node (ref "R14") (pin "2") (pinfunction "2_2") (pintype "passive"))
      (node (ref "R20") (pin "2") (pinfunction "2_2") (pintype "passive"))
      (node (ref "R27") (pin "2") (pinfunction "2_2") (pintype "passive"))
      (node (ref "R28") (pin "1") (pinfunction "1_1") (pintype "passive"))
      (node (ref "R8") (pin "2") (pinfunction "2_2") (pintype "passive"))
      (node (ref "U1") (pin "1") (pinfunction "GND_1") (pintype "passive"))
      (node (ref "U2") (pin "1") (pinfunction "GND_1") (pintype "passive"))
      (node (ref "U3") (pin "18") (pinfunction "GND_18") (pintype "power_in"))
      (node (ref "U3") (pin "28") (pinfunction "GND_28") (pintype "power_in"))
      (node (ref "U3") (pin "39") (pinfunction "GND_39") (pintype "power_in"))
      (node (ref "U3") (pin "6") (pinfunction "GND_6") (pintype "power_in"))
      (node (ref "U4") (pin "1") (pinfunction "GND_1") (pintype "power_in"))
      (node (ref "U4") (pin "4") (pinfunction "V-_(CASE)_4") (pintype "power_in"))
      (node (ref "U5") (pin "1") (pinfunction "GND_1") (pintype "power_in"))
      (node (ref "U5") (pin "4") (pinfunction "V-_(CASE)_4") (pintype "power_in"))
      (node (ref "U6") (pin "4") (pinfunction "V-_4") (pintype "power_in"))
      (node (ref "U8") (pin "2") (pinfunction "CATHODE_2") (pintype "passive"))
      (node (ref "U8") (pin "4") (pinfunction "ENITIER_4") (pintype "passive"))
      (node (ref "U9") (pin "2") (pinfunction "CATHODE_2") (pintype "passive"))
      (node (ref "U9") (pin "4") (pinfunction "ENITIER_4") (pintype "passive"))
    )
    (net (code "36") (name "GND_BAT") (class "Default")
      (node (ref "U7") (pin "1") (pinfunction "ISEN_A_1") (pintype "passive"))
      (node (ref "U7") (pin "15") (pinfunction "ISEN_B_15") (pintype "passive"))
      (node (ref "U7") (pin "8") (pinfunction "GND_8") (pintype "power_in"))
    )
    (net (code "37") (name "LARM_MV") (class "Default")
      (node (ref "JP1") (pin "3") (pinfunction "3_3") (pintype "passive"))
      (node (ref "JP4") (pin "4") (pinfunction "4_4") (pintype "passive"))
      (node (ref "P2") (pin "1") (pinfunction "1_1") (pintype "passive"))
      (node (ref "U3") (pin "11") (pinfunction "PD2_(PCINT/26/INT0)_11") (pintype "bidirectional"))
      (node (ref "U3") (pin "34") (pinfunction "PA3_(ADC3/PCINT3)_34") (pintype "bidirectional"))
    )
    (net (code "38") (name "Net-(1-Pad1)") (class "Default")
      (node (ref "1") (pin "1") (pinfunction "1_1") (pintype "passive"))
      (node (ref "C10") (pin "2") (pinfunction "2_2") (pintype "passive"))
      (node (ref "C8") (pin "2") (pinfunction "2_2") (pintype "passive"))
    )
    (net (code "39") (name "Net-(C18-Pad1)") (class "Default")
      (node (ref "C18") (pin "1") (pinfunction "1_1") (pintype "passive"))
      (node (ref "R26") (pin "1") (pinfunction "1_1") (pintype "passive"))
    )
    (net (code "40") (name "Net-(C18-Pad2)") (class "Default")
      (node (ref "C18") (pin "2") (pinfunction "2_2") (pintype "passive"))
      (node (ref "MK1") (pin "1") (pinfunction "1_1") (pintype "passive"))
      (node (ref "R25") (pin "2") (pinfunction "2_2") (pintype "passive"))
    )
    (net (code "41") (name "Net-(D1-A)") (class "Default")
      (node (ref "D1") (pin "1") (pinfunction "A_1") (pintype "passive"))
      (node (ref "D2") (pin "1") (pinfunction "A_1") (pintype "passive"))
    )
    (net (code "42") (name "Net-(D1-K)") (class "Default")
      (node (ref "C6") (pin "2") (pinfunction "2_2") (pintype "passive"))
      (node (ref "D1") (pin "2") (pinfunction "K_2") (pintype "passive"))
      (node (ref "R14") (pin "1") (pinfunction "1_1") (pintype "passive"))
      (node (ref "U4") (pin "3") (pinfunction "IN-_3") (pintype "input"))
    )
    (net (code "43") (name "Net-(D2-K)") (class "Default")
      (node (ref "D2") (pin "2") (pinfunction "K_2") (pintype "passive"))
      (node (ref "U4") (pin "2") (pinfunction "IN+_2") (pintype "input"))
    )
    (net (code "44") (name "Net-(D3-A)") (class "Default")
      (node (ref "D3") (pin "1") (pinfunction "A_1") (pintype "passive"))
      (node (ref "J6") (pin "1") (pinfunction "1_1") (pintype "passive"))
      (node (ref "Q10") (pin "3") (pinfunction "D_3") (pintype "passive"))
    )
    (net (code "45") (name "Net-(D4-A)") (class "Default")
      (node (ref "D4") (pin "1") (pinfunction "A_1") (pintype "passive"))
      (node (ref "J7") (pin "1") (pinfunction "1_1") (pintype "passive"))
      (node (ref "Q11") (pin "3") (pinfunction "D_3") (pintype "passive"))
    )
    (net (code "46") (name "Net-(D9-K)") (class "Default")
      (node (ref "D9") (pin "2") (pinfunction "K_2") (pintype "passive"))
      (node (ref "R35") (pin "2") (pinfunction "2_2") (pintype "passive"))
    )
    (net (code "47") (name "Net-(D10-K)") (class "Default")
      (node (ref "D10") (pin "2") (pinfunction "K_2") (pintype "passive"))
      (node (ref "R36") (pin "2") (pinfunction "2_2") (pintype "passive"))
    )
    (net (code "48") (name "Net-(D11-K)") (class "Default")
      (node (ref "D11") (pin "2") (pinfunction "K_2") (pintype "passive"))
      (node (ref "R37") (pin "2") (pinfunction "2_2") (pintype "passive"))
    )
    (net (code "49") (name "Net-(D13-K)") (class "Default")
      (node (ref "D13") (pin "2") (pinfunction "K_2") (pintype "passive"))
      (node (ref "D16") (pin "2") (pinfunction "K_2") (pintype "passive"))
      (node (ref "D5") (pin "1") (pinfunction "A_1") (pintype "passive"))
      (node (ref "D6") (pin "1") (pinfunction "A_1") (pintype "passive"))
      (node (ref "M1") (pin "2") (pinfunction "2_2") (pintype "passive"))
      (node (ref "M2") (pin "2") (pinfunction "2_2") (pintype "passive"))
      (node (ref "R36") (pin "1") (pinfunction "1_1") (pintype "passive"))
      (node (ref "R38") (pin "1") (pinfunction "1_1") (pintype "passive"))
      (node (ref "U7") (pin "14") (pinfunction "OUT4_14") (pintype "output"))
      (node (ref "U7") (pin "3") (pinfunction "OUT2_3") (pintype "output"))
    )
    (net (code "50") (name "Net-(D14-K)") (class "Default")
      (node (ref "D14") (pin "2") (pinfunction "K_2") (pintype "passive"))
      (node (ref "D8") (pin "1") (pinfunction "A_1") (pintype "passive"))
      (node (ref "M1") (pin "1") (pinfunction "1_1") (pintype "passive"))
      (node (ref "R37") (pin "1") (pinfunction "1_1") (pintype "passive"))
      (node (ref "U7") (pin "13") (pinfunction "OUT3_13") (pintype "output"))
    )
    (net (code "51") (name "Net-(D15-K)") (class "Default")
      (node (ref "D15") (pin "2") (pinfunction "K_2") (pintype "passive"))
      (node (ref "D7") (pin "1") (pinfunction "A_1") (pintype "passive"))
      (node (ref "M2") (pin "1") (pinfunction "1_1") (pintype "passive"))
      (node (ref "R35") (pin "1") (pinfunction "1_1") (pintype "passive"))
      (node (ref "U7") (pin "2") (pinfunction "OUT1_2") (pintype "output"))
    )
    (net (code "52") (name "Net-(J1-CD{slash}DAT3)") (class "Default")
      (node (ref "J1") (pin "2") (pinfunction "CD/DAT3_2") (pintype "passive"))
      (node (ref "R11") (pin "1") (pinfunction "1_1") (pintype "passive"))
      (node (ref "R12") (pin "1") (pinfunction "1_1") (pintype "passive"))
    )
    (net (code "53") (name "Net-(J1-CLK)") (class "Default")
      (node (ref "J1") (pin "5") (pinfunction "CLK_5") (pintype "passive"))
      (node (ref "R6") (pin "1") (pinfunction "1_1") (pintype "passive"))
      (node (ref "R8") (pin "1") (pinfunction "1_1") (pintype "passive"))
    )
    (net (code "54") (name "Net-(J1-CMD)") (class "Default")
      (node (ref "J1") (pin "3") (pinfunction "CMD_3") (pintype "passive"))
      (node (ref "R10") (pin "1") (pinfunction "1_1") (pintype "passive"))
      (node (ref "R9") (pin "1") (pinfunction "1_1") (pintype "passive"))
    )
    (net (code "55") (name "Net-(J5-Pad1)") (class "Default")
      (node (ref "J5") (pin "1") (pinfunction "1_1") (pintype "passive"))
      (node (ref "R27") (pin "1") (pinfunction "1_1") (pintype "passive"))
    )
    (net (code "56") (name "Net-(P1-Pad1)") (class "Default")
      (node (ref "P1") (pin "1") (pinfunction "1_1") (pintype "passive"))
      (node (ref "R1") (pin "2") (pinfunction "2_2") (pintype "passive"))
    )
    (net (code "57") (name "Net-(P1-Pad3)") (class "Default")
      (node (ref "P1") (pin "3") (pinfunction "3_3") (pintype "passive"))
      (node (ref "R2") (pin "2") (pinfunction "2_2") (pintype "passive"))
    )
    (net (code "58") (name "Net-(P1-Pad5)") (class "Default")
      (node (ref "P1") (pin "5") (pinfunction "5_5") (pintype "passive"))
      (node (ref "R3") (pin "2") (pinfunction "2_2") (pintype "passive"))
    )
    (net (code "59") (name "Net-(P1-Pad9)") (class "Default")
      (node (ref "P1") (pin "9") (pinfunction "9_9") (pintype "passive"))
      (node (ref "R5") (pin "2") (pinfunction "2_2") (pintype "passive"))
    )
    (net (code "60") (name "Net-(Q1-B)") (class "Default")
      (node (ref "Q1") (pin "1") (pinfunction "B_1") (pintype "passive"))
      (node (ref "R16") (pin "2") (pinfunction "2_2") (pintype "passive"))
    )
    (net (code "61") (name "Net-(Q1-C)") (class "Default")
      (node (ref "J4") (pin "1") (pinfunction "1_1") (pintype "passive"))
      (node (ref "Q1") (pin "3") (pinfunction "C_3") (pintype "passive"))
      (node (ref "Q6") (pin "3") (pinfunction "C_3") (pintype "passive"))
    )
    (net (code "62") (name "Net-(Q2-B)") (class "Default")
      (node (ref "Q2") (pin "1") (pinfunction "B_1") (pintype "passive"))
      (node (ref "R15") (pin "2") (pinfunction "2_2") (pintype "passive"))
    )
    (net (code "63") (name "Net-(Q2-C)") (class "Default")
      (node (ref "J4") (pin "2") (pinfunction "2_2") (pintype "passive"))
      (node (ref "Q2") (pin "3") (pinfunction "C_3") (pintype "passive"))
      (node (ref "Q7") (pin "3") (pinfunction "C_3") (pintype "passive"))
    )
    (net (code "64") (name "Net-(Q3-G)") (class "Default")
      (node (ref "C8") (pin "1") (pinfunction "1_1") (pintype "passive"))
      (node (ref "C9") (pin "2") (pinfunction "2_2") (pintype "passive"))
      (node (ref "Q3") (pin "1") (pinfunction "G_1") (pintype "passive"))
    )
    (net (code "65") (name "Net-(Q3-S)") (class "Default")
      (node (ref "Q3") (pin "2") (pinfunction "S_2") (pintype "passive"))
      (node (ref "R20") (pin "1") (pinfunction "1_1") (pintype "passive"))
    )
    (net (code "66") (name "Net-(Q4-C)") (class "Default")
      (node (ref "Q4") (pin "3") (pinfunction "C_3") (pintype "passive"))
      (node (ref "R16") (pin "1") (pinfunction "1_1") (pintype "passive"))
    )
    (net (code "67") (name "Net-(Q5-C)") (class "Default")
      (node (ref "Q5") (pin "3") (pinfunction "C_3") (pintype "passive"))
      (node (ref "R15") (pin "1") (pinfunction "1_1") (pintype "passive"))
    )
    (net (code "68") (name "Net-(Q8-B)") (class "Default")
      (node (ref "Q8") (pin "1") (pinfunction "B_1") (pintype "passive"))
      (node (ref "R31") (pin "1") (pinfunction "1_1") (pintype "passive"))
    )
    (net (code "69") (name "Net-(Q9-B)") (class "Default")
      (node (ref "Q9") (pin "1") (pinfunction "B_1") (pintype "passive"))
      (node (ref "R32") (pin "1") (pinfunction "1_1") (pintype "passive"))
    )
    (net (code "70") (name "Net-(Q10-G)") (class "Default")
      (node (ref "Q10") (pin "1") (pinfunction "G_1") (pintype "passive"))
      (node (ref "Q8") (pin "3") (pinfunction "C_3") (pintype "passive"))
      (node (ref "R33") (pin "1") (pinfunction "1_1") (pintype "passive"))
    )
    (net (code "71") (name "Net-(Q11-G)") (class "Default")
      (node (ref "Q11") (pin "1") (pinfunction "G_1") (pintype "passive"))
      (node (ref "Q9") (pin "3") (pinfunction "C_3") (pintype "passive"))
      (node (ref "R34") (pin "1") (pinfunction "1_1") (pintype "passive"))
    )
    (net (code "72") (name "Net-(R29-Pad2)") (class "Default")
      (node (ref "R29") (pin "2") (pinfunction "2_2") (pintype "passive"))
      (node (ref "R30") (pin "1") (pinfunction "1_1") (pintype "passive"))
    )
    (net (code "73") (name "Net-(U3-XTAL1)") (class "Default")
      (node (ref "C17") (pin "2") (pinfunction "2_2") (pintype "passive"))
      (node (ref "U3") (pin "8") (pinfunction "XTAL1_8") (pintype "passive"))
      (node (ref "X1") (pin "1") (pinfunction "OSC1_1") (pintype "passive"))
    )
    (net (code "74") (name "Net-(U3-XTAL2)") (class "Default")
      (node (ref "C14") (pin "2") (pinfunction "2_2") (pintype "passive"))
      (node (ref "U3") (pin "7") (pinfunction "XTAL2_7") (pintype "passive"))
      (node (ref "X1") (pin "2") (pinfunction "OSC2_2") (pintype "passive"))
    )
    (net (code "75") (name "Net-(U5-IN+)") (class "Default")
      (node (ref "J5") (pin "2") (pinfunction "2_2") (pintype "passive"))
      (node (ref "U5") (pin "2") (pinfunction "IN+_2") (pintype "input"))
    )
    (net (code "76") (name "Net-(U6A-IN+)") (class "Default")
      (node (ref "R28") (pin "2") (pinfunction "2_2") (pintype "passive"))
      (node (ref "R29") (pin "1") (pinfunction "1_1") (pintype "passive"))
      (node (ref "U6") (pin "3") (pinfunction "IN+_3") (pintype "input"))
    )
    (net (code "77") (name "Net-(U6A-IN-)") (class "Default")
      (node (ref "R23") (pin "1") (pinfunction "1_1") (pintype "passive"))
      (node (ref "R26") (pin "2") (pinfunction "2_2") (pintype "passive"))
      (node (ref "U6") (pin "2") (pinfunction "IN-_2") (pintype "input"))
    )
    (net (code "78") (name "Net-(U8-ANODE)") (class "Default")
      (node (ref "R42") (pin "1") (pinfunction "1_1") (pintype "passive"))
      (node (ref "U8") (pin "1") (pinfunction "ANODE_1") (pintype "passive"))
    )
    (net (code "79") (name "Net-(U9-ANODE)") (class "Default")
      (node (ref "2") (pin "1") (pinfunction "1_1") (pintype "passive"))
      (node (ref "U9") (pin "1") (pinfunction "ANODE_1") (pintype "passive"))
    )
    (net (code "80") (name "RARM_MV") (class "Default")
      (node (ref "JP1") (pin "4") (pinfunction "4_4") (pintype "passive"))
      (node (ref "JP4") (pin "5") (pinfunction "5_5") (pintype "passive"))
      (node (ref "P3") (pin "1") (pinfunction "1_1") (pintype "passive"))
      (node (ref "U3") (pin "12") (pinfunction "PD3_(PCINT/27/INT1)_12") (pintype "bidirectional"))
      (node (ref "U3") (pin "33") (pinfunction "PA4_(ADC4/PCINT4)_33") (pintype "bidirectional"))
    )
    (net (code "81") (name "V3") (class "Default")
      (node (ref "C1") (pin "1") (pinfunction "1_1") (pintype "passive"))
      (node (ref "C2") (pin "2") (pinfunction "2_2") (pintype "passive"))
      (node (ref "J1") (pin "4") (pinfunction "VDD_4") (pintype "passive"))
      (node (ref "JP2") (pin "4") (pinfunction "4_4") (pintype "passive"))
      (node (ref "U1") (pin "2") (pinfunction "OUT_2") (pintype "passive"))
    )
    (net (code "82") (name "VBAT") (class "Default")
      (node (ref "B1") (pin "2") (pintype "passive"))
      (node (ref "B1") (pin "5") (pintype "passive"))
      (node (ref "JP2") (pin "8") (pinfunction "8_8") (pintype "passive"))
    )
    (net (code "83") (name "VBATT") (class "Default")
      (node (ref "C11") (pin "2") (pinfunction "2_2") (pintype "passive"))
      (node (ref "C23") (pin "1") (pinfunction "1_1") (pintype "passive"))
      (node (ref "C24") (pin "1") (pinfunction "1_1") (pintype "passive"))
      (node (ref "C25") (pin "1") (pinfunction "1_1") (pintype "passive"))
      (node (ref "C27") (pin "1") (pinfunction "1_1") (pintype "passive"))
      (node (ref "D10") (pin "1") (pinfunction "A_1") (pintype "passive"))
      (node (ref "D11") (pin "1") (pinfunction "A_1") (pintype "passive"))
      (node (ref "D12") (pin "1") (pinfunction "A_1") (pintype "passive"))
      (node (ref "D3") (pin "2") (pinfunction "K_2") (pintype "passive"))
      (node (ref "D4") (pin "2") (pinfunction "K_2") (pintype "passive"))
      (node (ref "D5") (pin "2") (pinfunction "K_2") (pintype "passive"))
      (node (ref "D6") (pin "2") (pinfunction "K_2") (pintype "passive"))
      (node (ref "D7") (pin "2") (pinfunction "K_2") (pintype "passive"))
      (node (ref "D8") (pin "2") (pinfunction "K_2") (pintype "passive"))
      (node (ref "D9") (pin "1") (pinfunction "A_1") (pintype "passive"))
      (node (ref "J6") (pin "2") (pinfunction "2_2") (pintype "passive"))
      (node (ref "J7") (pin "2") (pinfunction "2_2") (pintype "passive"))
      (node (ref "U1") (pin "3") (pinfunction "IN_3") (pintype "passive"))
      (node (ref "U2") (pin "3") (pinfunction "IN_3") (pintype "passive"))
      (node (ref "U4") (pin "8") (pinfunction "V+_8") (pintype "power_in"))
      (node (ref "U7") (pin "4") (pinfunction "VS_4") (pintype "power_in"))
    )
    (net (code "84") (name "VCC") (class "Default")
      (node (ref "2") (pin "2") (pinfunction "2_2") (pintype "passive"))
      (node (ref "C12") (pin "2") (pinfunction "2_2") (pintype "passive"))
      (node (ref "C13") (pin "2") (pinfunction "2_2") (pintype "passive"))
      (node (ref "C15") (pin "1") (pinfunction "1_1") (pintype "passive"))
      (node (ref "C16") (pin "2") (pinfunction "2_2") (pintype "passive"))
      (node (ref "C19") (pin "2") (pinfunction "2_2") (pintype "passive"))
      (node (ref "C21") (pin "2") (pinfunction "2_2") (pintype "passive"))
      (node (ref "C26") (pin "1") (pinfunction "1_1") (pintype "passive"))
      (node (ref "C3") (pin "1") (pinfunction "1_1") (pintype "passive"))
      (node (ref "C4") (pin "2") (pinfunction "2_2") (pintype "passive"))
      (node (ref "J3") (pin "2") (pinfunction "2_2") (pintype "passive"))
      (node (ref "JP2") (pin "2") (pinfunction "2_2") (pintype "passive"))
      (node (ref "JP2") (pin "5") (pinfunction "5_5") (pintype "passive"))
      (node (ref "P2") (pin "2") (pinfunction "2_2") (pintype "passive"))
      (node (ref "P3") (pin "2") (pinfunction "2_2") (pintype "passive"))
      (node (ref "Q1") (pin "2") (pinfunction "E_2") (pintype "passive"))
      (node (ref "Q2") (pin "2") (pinfunction "E_2") (pintype "passive"))
      (node (ref "Q3") (pin "3") (pinfunction "D_3") (pintype "passive"))
      (node (ref "R1") (pin "1") (pinfunction "1_1") (pintype "passive"))
      (node (ref "R13") (pin "1") (pinfunction "1_1") (pintype "passive"))
      (node (ref "R17") (pin "1") (pinfunction "1_1") (pintype "passive"))
      (node (ref "R2") (pin "1") (pinfunction "1_1") (pintype "passive"))
      (node (ref "R24") (pin "1") (pinfunction "1_1") (pintype "passive"))
      (node (ref "R25") (pin "1") (pinfunction "1_1") (pintype "passive"))
      (node (ref "R3") (pin "1") (pinfunction "1_1") (pintype "passive"))
      (node (ref "R30") (pin "2") (pinfunction "2_2") (pintype "passive"))
      (node (ref "R4") (pin "1") (pinfunction "1_1") (pintype "passive"))
      (node (ref "R42") (pin "2") (pinfunction "2_2") (pintype "passive"))
      (node (ref "R43") (pin "2") (pinfunction "2_2") (pintype "passive"))
      (node (ref "R44") (pin "2") (pinfunction "2_2") (pintype "passive"))
      (node (ref "R5") (pin "1") (pinfunction "1_1") (pintype "passive"))
      (node (ref "R7") (pin "1") (pinfunction "1_1") (pintype "passive"))
      (node (ref "U2") (pin "2") (pinfunction "OUT_2") (pintype "passive"))
      (node (ref "U3") (pin "17") (pinfunction "VCC_17") (pintype "power_in"))
      (node (ref "U3") (pin "27") (pinfunction "AVCC_27") (pintype "power_in"))
      (node (ref "U3") (pin "38") (pinfunction "VCC_38") (pintype "power_in"))
      (node (ref "U3") (pin "5") (pinfunction "VCC_5") (pintype "power_in"))
      (node (ref "U5") (pin "3") (pinfunction "IN-_3") (pintype "input"))
      (node (ref "U6") (pin "8") (pinfunction "V+_8") (pintype "power_in"))
      (node (ref "U7") (pin "9") (pinfunction "VSS_9") (pintype "power_in"))
    )
    (net (code "85") (name "Vb") (class "Default")
      (node (ref "B1") (pin "3") (pintype "passive"))
      (node (ref "B1") (pin "4") (pintype "passive"))
      (node (ref "BAT1") (pin "2") (pinfunction "2_2") (pintype "passive"))
    )
    (net (code "86") (name "unconnected-(B1-Pad1)") (class "Default")
      (node (ref "B1") (pin "1") (pintype "passive+no_connect"))
    )
    (net (code "87") (name "unconnected-(B1-Pad6)") (class "Default")
      (node (ref "B1") (pin "6") (pintype "passive+no_connect"))
    )
    (net (code "88") (name "unconnected-(D12-K-Pad2)") (class "Default")
      (node (ref "D12") (pin "2") (pinfunction "K_2") (pintype "passive"))
    )
    (net (code "89") (name "unconnected-(J1-DAT1-Pad8)") (class "Default")
      (node (ref "J1") (pin "8") (pinfunction "DAT1_8") (pintype "passive+no_connect"))
    )
    (net (code "90") (name "unconnected-(J1-DAT2-Pad1)") (class "Default")
      (node (ref "J1") (pin "1") (pinfunction "DAT2_1") (pintype "passive+no_connect"))
    )
    (net (code "91") (name "unconnected-(J1-Pad9)") (class "Default")
      (node (ref "J1") (pin "9") (pinfunction "9_9") (pintype "passive+no_connect"))
    )
    (net (code "92") (name "unconnected-(J1-Pad10)") (class "Default")
      (node (ref "J1") (pin "10") (pinfunction "10_10") (pintype "passive+no_connect"))
    )
    (net (code "93") (name "unconnected-(J1-Pad11)") (class "Default")
      (node (ref "J1") (pin "11") (pinfunction "11_11") (pintype "passive+no_connect"))
    )
    (net (code "94") (name "unconnected-(J1-Pad12)") (class "Default")
      (node (ref "J1") (pin "12") (pinfunction "12_12") (pintype "passive+no_connect"))
    )
    (net (code "95") (name "unconnected-(J2-Pad1)") (class "Default")
      (node (ref "J2") (pin "1") (pinfunction "1_1") (pintype "passive+no_connect"))
    )
    (net (code "96") (name "unconnected-(J2-Pad6)") (class "Default")
      (node (ref "J2") (pin "6") (pinfunction "6_6") (pintype "passive+no_connect"))
    )
    (net (code "97") (name "unconnected-(JP1-Pad9)") (class "Default")
      (node (ref "JP1") (pin "9") (pinfunction "9_9") (pintype "passive"))
    )
    (net (code "98") (name "unconnected-(JP1-Pad10)") (class "Default")
      (node (ref "JP1") (pin "10") (pinfunction "10_10") (pintype "passive"))
    )
    (net (code "99") (name "unconnected-(JP2-Pad1)") (class "Default")
      (node (ref "JP2") (pin "1") (pinfunction "1_1") (pintype "passive+no_connect"))
    )
    (net (code "100") (name "unconnected-(Q4-B-Pad1)") (class "Default")
      (node (ref "Q4") (pin "1") (pinfunction "B_1") (pintype "passive"))
    )
    (net (code "101") (name "unconnected-(Q5-B-Pad1)") (class "Default")
      (node (ref "Q5") (pin "1") (pinfunction "B_1") (pintype "passive"))
    )
    (net (code "102") (name "unconnected-(Q6-B-Pad1)") (class "Default")
      (node (ref "Q6") (pin "1") (pinfunction "B_1") (pintype "passive"))
    )
    (net (code "103") (name "unconnected-(Q7-B-Pad1)") (class "Default")
      (node (ref "Q7") (pin "1") (pinfunction "B_1") (pintype "passive"))
    )
    (net (code "104") (name "unconnected-(R18-Pad2)") (class "Default")
      (node (ref "R18") (pin "2") (pinfunction "2_2") (pintype "passive"))
    )
    (net (code "105") (name "unconnected-(R19-Pad2)") (class "Default")
      (node (ref "R19") (pin "2") (pinfunction "2_2") (pintype "passive"))
    )
    (net (code "106") (name "unconnected-(R21-Pad1)") (class "Default")
      (node (ref "R21") (pin "1") (pinfunction "1_1") (pintype "passive"))
    )
    (net (code "107") (name "unconnected-(R21-Pad2)") (class "Default")
      (node (ref "R21") (pin "2") (pinfunction "2_2") (pintype "passive"))
    )
    (net (code "108") (name "unconnected-(R22-Pad1)") (class "Default")
      (node (ref "R22") (pin "1") (pinfunction "1_1") (pintype "passive"))
    )
    (net (code "109") (name "unconnected-(R22-Pad2)") (class "Default")
      (node (ref "R22") (pin "2") (pinfunction "2_2") (pintype "passive"))
    )
    (net (code "110") (name "unconnected-(R38-Pad2)") (class "Default")
      (node (ref "R38") (pin "2") (pinfunction "2_2") (pintype "passive"))
    )
    (net (code "111") (name "unconnected-(U4-BAL-Pad5)") (class "Default")
      (node (ref "U4") (pin "5") (pinfunction "BAL_5") (pintype "passive"))
    )
    (net (code "112") (name "unconnected-(U4-BAL{slash}STB-Pad6)") (class "Default")
      (node (ref "U4") (pin "6") (pinfunction "BAL/STB_6") (pintype "passive"))
    )
    (net (code "113") (name "unconnected-(U5-BAL-Pad5)") (class "Default")
      (node (ref "U5") (pin "5") (pinfunction "BAL_5") (pintype "passive"))
    )
    (net (code "114") (name "unconnected-(U5-BAL{slash}STB-Pad6)") (class "Default")
      (node (ref "U5") (pin "6") (pinfunction "BAL/STB_6") (pintype "passive"))
    )
    (net (code "115") (name "unconnected-(U5-V+-Pad8)") (class "Default")
      (node (ref "U5") (pin "8") (pinfunction "V+_8") (pintype "power_in"))
    )
  )
)
